# Interface1.net
KiCad netlist of a schematic drawn in Altium Designer
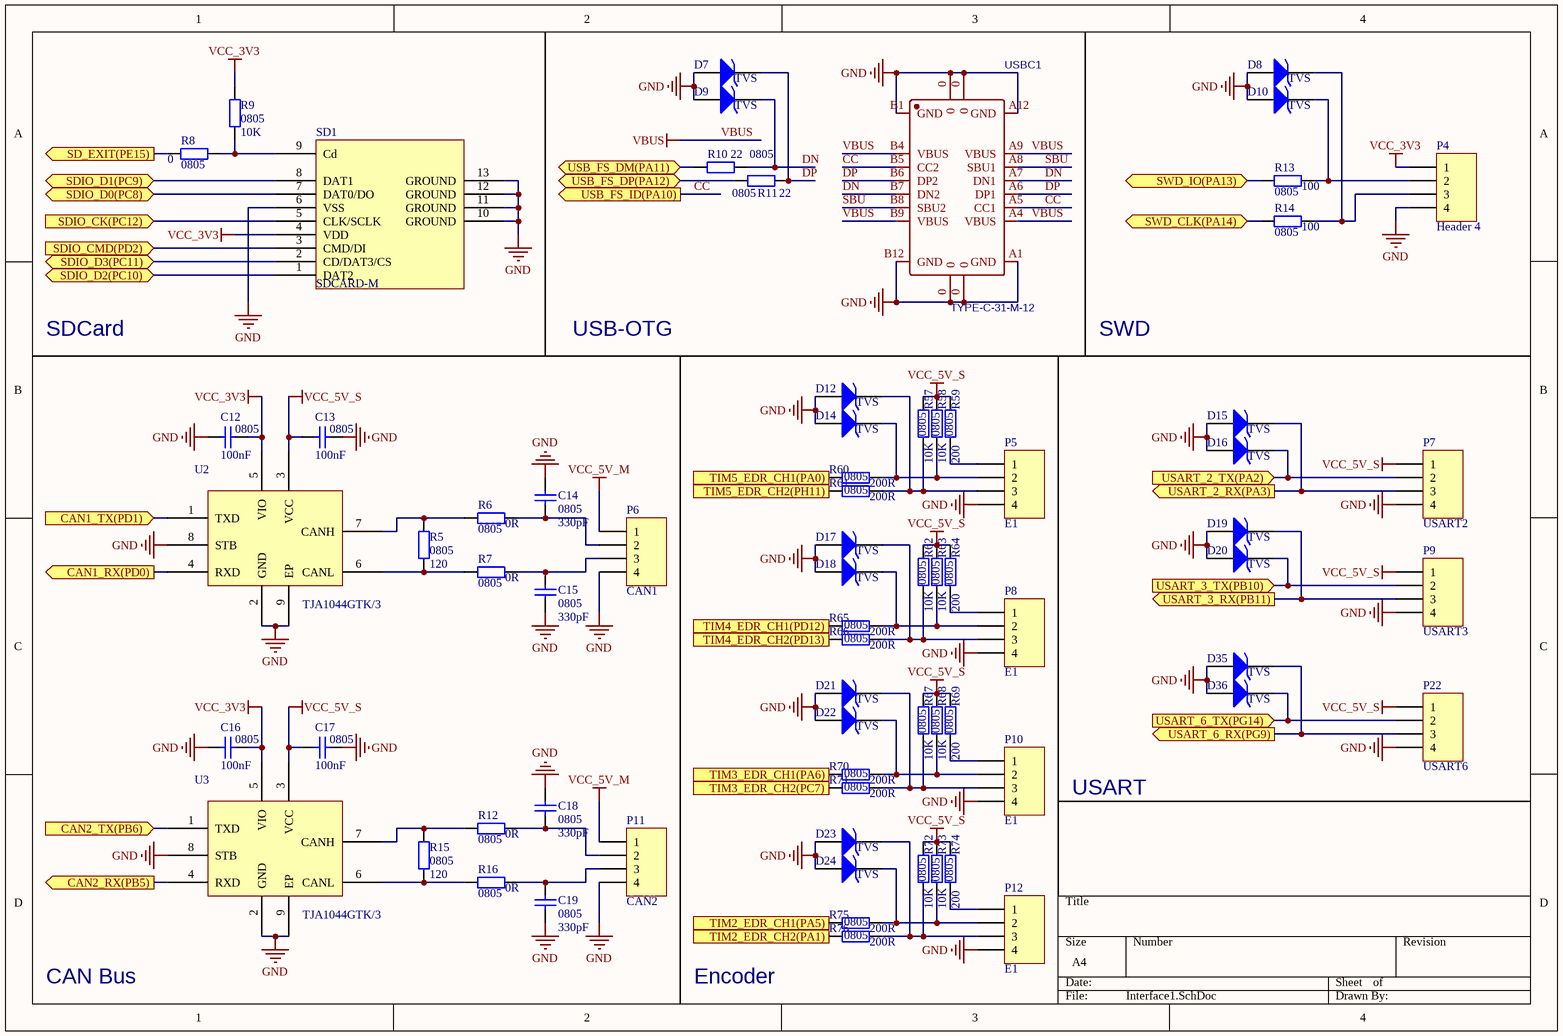
[diagram p0: Interface1.SchDoc]

(export (version "E")
  (design (tool "Eeschema 10.0.6"))
  (components
    (comp (ref "C12")
      (value "0805")
      (footprint "C 0805_M")
      (fields (field (name "ALTIUM_VALUE") "100nF"))
      (libsource (lib "QT") (part "CAP"))
    )
    (comp (ref "C13")
      (value "0805")
      (footprint "C 0805_M")
      (fields (field (name "ALTIUM_VALUE") "100nF"))
      (libsource (lib "QT") (part "CAP"))
    )
    (comp (ref "C14")
      (value "0805")
      (footprint "C 0805_M")
      (fields (field (name "ALTIUM_VALUE") "330pF"))
      (libsource (lib "QT") (part "CAP"))
    )
    (comp (ref "C15")
      (value "0805")
      (footprint "C 0805_M")
      (fields (field (name "ALTIUM_VALUE") "330pF"))
      (libsource (lib "QT") (part "CAP"))
    )
    (comp (ref "C16")
      (value "0805")
      (footprint "C 0805_M")
      (fields (field (name "ALTIUM_VALUE") "100nF"))
      (libsource (lib "QT") (part "CAP"))
    )
    (comp (ref "C17")
      (value "0805")
      (footprint "C 0805_M")
      (fields (field (name "ALTIUM_VALUE") "100nF"))
      (libsource (lib "QT") (part "CAP"))
    )
    (comp (ref "C18")
      (value "0805")
      (footprint "C 0805_M")
      (fields (field (name "ALTIUM_VALUE") "330pF"))
      (libsource (lib "QT") (part "CAP"))
    )
    (comp (ref "C19")
      (value "0805")
      (footprint "C 0805_M")
      (fields (field (name "ALTIUM_VALUE") "330pF"))
      (libsource (lib "QT") (part "CAP"))
    )
    (comp (ref "D7")
      (value "TVS")
      (footprint "SOD-523")
      (description "High Conductance Fast Diode")
      (fields (field (name "PUBLISHER") "Altium Limited"))
      (libsource (lib "QT") (part "D"))
    )
    (comp (ref "D8")
      (value "TVS")
      (footprint "SOD-523")
      (description "High Conductance Fast Diode")
      (fields (field (name "PUBLISHER") "Altium Limited"))
      (libsource (lib "QT") (part "D"))
    )
    (comp (ref "D9")
      (value "TVS")
      (footprint "SOD-523")
      (description "High Conductance Fast Diode")
      (fields (field (name "PUBLISHER") "Altium Limited"))
      (libsource (lib "QT") (part "D"))
    )
    (comp (ref "D10")
      (value "TVS")
      (footprint "SOD-523")
      (description "High Conductance Fast Diode")
      (fields (field (name "PUBLISHER") "Altium Limited"))
      (libsource (lib "QT") (part "D"))
    )
    (comp (ref "D12")
      (value "TVS")
      (footprint "SOD-523")
      (description "High Conductance Fast Diode")
      (fields (field (name "PUBLISHER") "Altium Limited"))
      (libsource (lib "QT") (part "D"))
    )
    (comp (ref "D14")
      (value "TVS")
      (footprint "SOD-523")
      (description "High Conductance Fast Diode")
      (fields (field (name "PUBLISHER") "Altium Limited"))
      (libsource (lib "QT") (part "D"))
    )
    (comp (ref "D15")
      (value "TVS")
      (footprint "SOD-523")
      (description "High Conductance Fast Diode")
      (fields (field (name "PUBLISHER") "Altium Limited"))
      (libsource (lib "QT") (part "D"))
    )
    (comp (ref "D16")
      (value "TVS")
      (footprint "SOD-523")
      (description "High Conductance Fast Diode")
      (fields (field (name "PUBLISHER") "Altium Limited"))
      (libsource (lib "QT") (part "D"))
    )
    (comp (ref "D17")
      (value "TVS")
      (footprint "SOD-523")
      (description "High Conductance Fast Diode")
      (fields (field (name "PUBLISHER") "Altium Limited"))
      (libsource (lib "QT") (part "D"))
    )
    (comp (ref "D18")
      (value "TVS")
      (footprint "SOD-523")
      (description "High Conductance Fast Diode")
      (fields (field (name "PUBLISHER") "Altium Limited"))
      (libsource (lib "QT") (part "D"))
    )
    (comp (ref "D19")
      (value "TVS")
      (footprint "SOD-523")
      (description "High Conductance Fast Diode")
      (fields (field (name "PUBLISHER") "Altium Limited"))
      (libsource (lib "QT") (part "D"))
    )
    (comp (ref "D20")
      (value "TVS")
      (footprint "SOD-523")
      (description "High Conductance Fast Diode")
      (fields (field (name "PUBLISHER") "Altium Limited"))
      (libsource (lib "QT") (part "D"))
    )
    (comp (ref "D21")
      (value "TVS")
      (footprint "SOD-523")
      (description "High Conductance Fast Diode")
      (fields (field (name "PUBLISHER") "Altium Limited"))
      (libsource (lib "QT") (part "D"))
    )
    (comp (ref "D22")
      (value "TVS")
      (footprint "SOD-523")
      (description "High Conductance Fast Diode")
      (fields (field (name "PUBLISHER") "Altium Limited"))
      (libsource (lib "QT") (part "D"))
    )
    (comp (ref "D23")
      (value "TVS")
      (footprint "SOD-523")
      (description "High Conductance Fast Diode")
      (fields (field (name "PUBLISHER") "Altium Limited"))
      (libsource (lib "QT") (part "D"))
    )
    (comp (ref "D24")
      (value "TVS")
      (footprint "SOD-523")
      (description "High Conductance Fast Diode")
      (fields (field (name "PUBLISHER") "Altium Limited"))
      (libsource (lib "QT") (part "D"))
    )
    (comp (ref "D35")
      (value "TVS")
      (footprint "SOD-523")
      (description "High Conductance Fast Diode")
      (fields (field (name "PUBLISHER") "Altium Limited"))
      (libsource (lib "QT") (part "D"))
    )
    (comp (ref "D36")
      (value "TVS")
      (footprint "SOD-523")
      (description "High Conductance Fast Diode")
      (fields (field (name "PUBLISHER") "Altium Limited"))
      (libsource (lib "QT") (part "D"))
    )
    (comp (ref "P4")
      (value "Header 4")
      (footprint "HDR2.54-LI-4P")
      (description "Header, 4-Pin")
      (fields (field (name "PUBLISHER") "Altium Limited"))
      (libsource (lib "QT") (part "Header 4"))
    )
    (comp (ref "P5")
      (value "E1")
      (footprint "HDR2.54-LI-4P")
      (description "Header, 4-Pin")
      (fields (field (name "PUBLISHER") "Altium Limited"))
      (libsource (lib "QT") (part "Header 4"))
    )
    (comp (ref "P6")
      (value "CAN1")
      (footprint "HDR2.54-LI-4P")
      (description "Header, 4-Pin")
      (fields (field (name "PUBLISHER") "Altium Limited"))
      (libsource (lib "QT") (part "Header 4"))
    )
    (comp (ref "P7")
      (value "USART2")
      (footprint "HDR2.54-LI-4P")
      (description "Header, 4-Pin")
      (fields (field (name "PUBLISHER") "Altium Limited"))
      (libsource (lib "QT") (part "Header 4"))
    )
    (comp (ref "P8")
      (value "E1")
      (footprint "HDR2.54-LI-4P")
      (description "Header, 4-Pin")
      (fields (field (name "PUBLISHER") "Altium Limited"))
      (libsource (lib "QT") (part "Header 4"))
    )
    (comp (ref "P9")
      (value "USART3")
      (footprint "HDR2.54-LI-4P")
      (description "Header, 4-Pin")
      (fields (field (name "PUBLISHER") "Altium Limited"))
      (libsource (lib "QT") (part "Header 4"))
    )
    (comp (ref "P10")
      (value "E1")
      (footprint "HDR2.54-LI-4P")
      (description "Header, 4-Pin")
      (fields (field (name "PUBLISHER") "Altium Limited"))
      (libsource (lib "QT") (part "Header 4"))
    )
    (comp (ref "P11")
      (value "CAN2")
      (footprint "HDR2.54-LI-4P")
      (description "Header, 4-Pin")
      (fields (field (name "PUBLISHER") "Altium Limited"))
      (libsource (lib "QT") (part "Header 4"))
    )
    (comp (ref "P12")
      (value "E1")
      (footprint "HDR2.54-LI-4P")
      (description "Header, 4-Pin")
      (fields (field (name "PUBLISHER") "Altium Limited"))
      (libsource (lib "QT") (part "Header 4"))
    )
    (comp (ref "P22")
      (value "USART6")
      (footprint "HDR2.54-LI-4P")
      (description "Header, 4-Pin")
      (fields (field (name "PUBLISHER") "Altium Limited"))
      (libsource (lib "QT") (part "Header 4"))
    )
    (comp (ref "R5")
      (value "0805")
      (footprint "R 0805_L")
      (description "Resistor")
      (fields (field (name "ALTIUM_VALUE") "120") (field (name "PUBLISHER") "Altium Limited"))
      (libsource (lib "QT") (part "RES2"))
    )
    (comp (ref "R6")
      (value "0805")
      (footprint "R 0805_L")
      (description "Resistor")
      (fields (field (name "ALTIUM_VALUE") "0R") (field (name "PUBLISHER") "Altium Limited"))
      (libsource (lib "") (part "RES2_1"))
    )
    (comp (ref "R7")
      (value "0805")
      (footprint "R 0805_L")
      (description "Resistor")
      (fields (field (name "ALTIUM_VALUE") "0R") (field (name "PUBLISHER") "Altium Limited"))
      (libsource (lib "") (part "RES2_1"))
    )
    (comp (ref "R8")
      (value "0805")
      (footprint "R 0805_L")
      (description "Resistor")
      (fields (field (name "ALTIUM_VALUE") "0") (field (name "PUBLISHER") "Altium Limited"))
      (libsource (lib "") (part "RES2_2"))
    )
    (comp (ref "R9")
      (value "0805")
      (footprint "R 0805_L")
      (description "Resistor")
      (fields (field (name "ALTIUM_VALUE") "10K") (field (name "PUBLISHER") "Altium Limited"))
      (libsource (lib "QT") (part "RES2"))
    )
    (comp (ref "R10")
      (value "0805")
      (footprint "R 0805_L")
      (description "Resistor")
      (fields (field (name "ALTIUM_VALUE") "22") (field (name "PUBLISHER") "Altium Limited"))
      (libsource (lib "") (part "RES2_2"))
    )
    (comp (ref "R11")
      (value "0805")
      (footprint "R 0805_L")
      (description "Resistor")
      (fields (field (name "ALTIUM_VALUE") "22") (field (name "PUBLISHER") "Altium Limited"))
      (libsource (lib "") (part "RES2_2"))
    )
    (comp (ref "R12")
      (value "0805")
      (footprint "R 0805_L")
      (description "Resistor")
      (fields (field (name "ALTIUM_VALUE") "0R") (field (name "PUBLISHER") "Altium Limited"))
      (libsource (lib "") (part "RES2_1"))
    )
    (comp (ref "R13")
      (value "0805")
      (footprint "R 0805_L")
      (description "Resistor")
      (fields (field (name "ALTIUM_VALUE") "100") (field (name "PUBLISHER") "Altium Limited"))
      (libsource (lib "") (part "RES2_2"))
    )
    (comp (ref "R14")
      (value "0805")
      (footprint "R 0805_L")
      (description "Resistor")
      (fields (field (name "ALTIUM_VALUE") "100") (field (name "PUBLISHER") "Altium Limited"))
      (libsource (lib "") (part "RES2_2"))
    )
    (comp (ref "R15")
      (value "0805")
      (footprint "R 0805_L")
      (description "Resistor")
      (fields (field (name "ALTIUM_VALUE") "120") (field (name "PUBLISHER") "Altium Limited"))
      (libsource (lib "QT") (part "RES2"))
    )
    (comp (ref "R16")
      (value "0805")
      (footprint "R 0805_L")
      (description "Resistor")
      (fields (field (name "ALTIUM_VALUE") "0R") (field (name "PUBLISHER") "Altium Limited"))
      (libsource (lib "") (part "RES2_1"))
    )
    (comp (ref "R57")
      (value "0805")
      (footprint "R 0805_L")
      (description "Resistor")
      (fields (field (name "ALTIUM_VALUE") "10K") (field (name "PUBLISHER") "Altium Limited"))
      (libsource (lib "QT") (part "RES2"))
    )
    (comp (ref "R58")
      (value "0805")
      (footprint "R 0805_L")
      (description "Resistor")
      (fields (field (name "ALTIUM_VALUE") "10K") (field (name "PUBLISHER") "Altium Limited"))
      (libsource (lib "QT") (part "RES2"))
    )
    (comp (ref "R59")
      (value "0805")
      (footprint "R 0805_L")
      (description "Resistor")
      (fields (field (name "ALTIUM_VALUE") "200") (field (name "PUBLISHER") "Altium Limited"))
      (libsource (lib "QT") (part "RES2"))
    )
    (comp (ref "R60")
      (value "0805")
      (footprint "R 0805_L")
      (description "Resistor")
      (fields (field (name "ALTIUM_VALUE") "200R") (field (name "PUBLISHER") "Altium Limited"))
      (libsource (lib "") (part "RES2_2"))
    )
    (comp (ref "R61")
      (value "0805")
      (footprint "R 0805_L")
      (description "Resistor")
      (fields (field (name "ALTIUM_VALUE") "200R") (field (name "PUBLISHER") "Altium Limited"))
      (libsource (lib "") (part "RES2_2"))
    )
    (comp (ref "R62")
      (value "0805")
      (footprint "R 0805_L")
      (description "Resistor")
      (fields (field (name "ALTIUM_VALUE") "10K") (field (name "PUBLISHER") "Altium Limited"))
      (libsource (lib "QT") (part "RES2"))
    )
    (comp (ref "R63")
      (value "0805")
      (footprint "R 0805_L")
      (description "Resistor")
      (fields (field (name "ALTIUM_VALUE") "10K") (field (name "PUBLISHER") "Altium Limited"))
      (libsource (lib "QT") (part "RES2"))
    )
    (comp (ref "R64")
      (value "0805")
      (footprint "R 0805_L")
      (description "Resistor")
      (fields (field (name "ALTIUM_VALUE") "200") (field (name "PUBLISHER") "Altium Limited"))
      (libsource (lib "QT") (part "RES2"))
    )
    (comp (ref "R65")
      (value "0805")
      (footprint "R 0805_L")
      (description "Resistor")
      (fields (field (name "ALTIUM_VALUE") "200R") (field (name "PUBLISHER") "Altium Limited"))
      (libsource (lib "") (part "RES2_2"))
    )
    (comp (ref "R66")
      (value "0805")
      (footprint "R 0805_L")
      (description "Resistor")
      (fields (field (name "ALTIUM_VALUE") "200R") (field (name "PUBLISHER") "Altium Limited"))
      (libsource (lib "") (part "RES2_2"))
    )
    (comp (ref "R67")
      (value "0805")
      (footprint "R 0805_L")
      (description "Resistor")
      (fields (field (name "ALTIUM_VALUE") "10K") (field (name "PUBLISHER") "Altium Limited"))
      (libsource (lib "QT") (part "RES2"))
    )
    (comp (ref "R68")
      (value "0805")
      (footprint "R 0805_L")
      (description "Resistor")
      (fields (field (name "ALTIUM_VALUE") "10K") (field (name "PUBLISHER") "Altium Limited"))
      (libsource (lib "QT") (part "RES2"))
    )
    (comp (ref "R69")
      (value "0805")
      (footprint "R 0805_L")
      (description "Resistor")
      (fields (field (name "ALTIUM_VALUE") "200") (field (name "PUBLISHER") "Altium Limited"))
      (libsource (lib "QT") (part "RES2"))
    )
    (comp (ref "R70")
      (value "0805")
      (footprint "R 0805_L")
      (description "Resistor")
      (fields (field (name "ALTIUM_VALUE") "200R") (field (name "PUBLISHER") "Altium Limited"))
      (libsource (lib "") (part "RES2_2"))
    )
    (comp (ref "R71")
      (value "0805")
      (footprint "R 0805_L")
      (description "Resistor")
      (fields (field (name "ALTIUM_VALUE") "200R") (field (name "PUBLISHER") "Altium Limited"))
      (libsource (lib "") (part "RES2_2"))
    )
    (comp (ref "R72")
      (value "0805")
      (footprint "R 0805_L")
      (description "Resistor")
      (fields (field (name "ALTIUM_VALUE") "10K") (field (name "PUBLISHER") "Altium Limited"))
      (libsource (lib "QT") (part "RES2"))
    )
    (comp (ref "R73")
      (value "0805")
      (footprint "R 0805_L")
      (description "Resistor")
      (fields (field (name "ALTIUM_VALUE") "10K") (field (name "PUBLISHER") "Altium Limited"))
      (libsource (lib "QT") (part "RES2"))
    )
    (comp (ref "R74")
      (value "0805")
      (footprint "R 0805_L")
      (description "Resistor")
      (fields (field (name "ALTIUM_VALUE") "200") (field (name "PUBLISHER") "Altium Limited"))
      (libsource (lib "QT") (part "RES2"))
    )
    (comp (ref "R75")
      (value "0805")
      (footprint "R 0805_L")
      (description "Resistor")
      (fields (field (name "ALTIUM_VALUE") "200R") (field (name "PUBLISHER") "Altium Limited"))
      (libsource (lib "") (part "RES2_2"))
    )
    (comp (ref "R76")
      (value "0805")
      (footprint "R 0805_L")
      (description "Resistor")
      (fields (field (name "ALTIUM_VALUE") "200R") (field (name "PUBLISHER") "Altium Limited"))
      (libsource (lib "") (part "RES2_2"))
    )
    (comp (ref "SD1")
      (value "SDCARD-M")
      (footprint "SDCARD-M")
      (description "TF卡槽")
      (libsource (lib "Fszhang") (part "SDCARD-M"))
    )
    (comp (ref "U2")
      (value "TJA1044GTK/3")
      (footprint "HVSON8")
      (libsource (lib "常用元件库") (part "TJA1044GTK/3"))
    )
    (comp (ref "U3")
      (value "TJA1044GTK/3")
      (footprint "HVSON8")
      (libsource (lib "常用元件库") (part "TJA1044GTK/3"))
    )
    (comp (ref "USBC1")
      (value "TYPE-C-31-M-12")
      (footprint "TYPE-C-USB-17")
      (libsource (lib "Interface") (part "TYPE-C-31-M-12"))
    )
  )
  (nets
    (net (code "1") (name "/CAN1_RX(PD0)") (class "Default")
      (node (ref "U2") (pin "4") (pinfunction "RXD_4") (pintype "passive"))
    )
    (net (code "2") (name "/CAN1_TX(PD1)") (class "Default")
      (node (ref "U2") (pin "1") (pinfunction "TXD_1") (pintype "passive"))
    )
    (net (code "3") (name "/CAN2_RX(PB5)") (class "Default")
      (node (ref "U3") (pin "4") (pinfunction "RXD_4") (pintype "passive"))
    )
    (net (code "4") (name "/CAN2_TX(PB6)") (class "Default")
      (node (ref "U3") (pin "1") (pinfunction "TXD_1") (pintype "passive"))
    )
    (net (code "5") (name "/CC") (class "Default")
      (node (ref "USBC1") (pin "A5") (pinfunction "CC1_A5") (pintype "passive"))
      (node (ref "USBC1") (pin "B5") (pinfunction "CC2_B5") (pintype "passive"))
    )
    (net (code "6") (name "/DN") (class "Default")
      (node (ref "D9") (pin "2") (pinfunction "K_2") (pintype "passive"))
      (node (ref "R10") (pin "2") (pinfunction "2_2") (pintype "passive"))
      (node (ref "USBC1") (pin "A7") (pinfunction "DN1_A7") (pintype "passive"))
      (node (ref "USBC1") (pin "B7") (pinfunction "DN2_B7") (pintype "passive"))
    )
    (net (code "7") (name "/DP") (class "Default")
      (node (ref "D7") (pin "2") (pinfunction "K_2") (pintype "passive"))
      (node (ref "R11") (pin "2") (pinfunction "2_2") (pintype "passive"))
      (node (ref "USBC1") (pin "A6") (pinfunction "DP1_A6") (pintype "passive"))
      (node (ref "USBC1") (pin "B6") (pinfunction "DP2_B6") (pintype "passive"))
    )
    (net (code "8") (name "/SBU") (class "Default")
      (node (ref "USBC1") (pin "A8") (pinfunction "SBU1_A8") (pintype "passive"))
      (node (ref "USBC1") (pin "B8") (pinfunction "SBU2_B8") (pintype "passive"))
    )
    (net (code "9") (name "/SDIO_CK(PC12)") (class "Default")
      (node (ref "SD1") (pin "5") (pinfunction "CLK/SCLK_5") (pintype "passive"))
    )
    (net (code "10") (name "/SDIO_CMD(PD2)") (class "Default")
      (node (ref "SD1") (pin "3") (pinfunction "CMD/DI_3") (pintype "passive"))
    )
    (net (code "11") (name "/SDIO_D0(PC8)") (class "Default")
      (node (ref "SD1") (pin "7") (pinfunction "DAT0/DO_7") (pintype "passive"))
    )
    (net (code "12") (name "/SDIO_D1(PC9)") (class "Default")
      (node (ref "SD1") (pin "8") (pinfunction "DAT1_8") (pintype "passive"))
    )
    (net (code "13") (name "/SDIO_D2(PC10)") (class "Default")
      (node (ref "SD1") (pin "1") (pinfunction "DAT2_1") (pintype "passive"))
    )
    (net (code "14") (name "/SDIO_D3(PC11)") (class "Default")
      (node (ref "SD1") (pin "2") (pinfunction "CD/DAT3/CS_2") (pintype "passive"))
    )
    (net (code "15") (name "/SD_EXIT(PE15)") (class "Default")
      (node (ref "R8") (pin "1") (pinfunction "1_1") (pintype "passive"))
    )
    (net (code "16") (name "/SWD_CLK(PA14)") (class "Default")
      (node (ref "R14") (pin "1") (pinfunction "1_1") (pintype "passive"))
    )
    (net (code "17") (name "/SWD_IO(PA13)") (class "Default")
      (node (ref "R13") (pin "1") (pinfunction "1_1") (pintype "passive"))
    )
    (net (code "18") (name "/TIM2_EDR_CH1(PA5)") (class "Default")
      (node (ref "R75") (pin "1") (pinfunction "1_1") (pintype "passive"))
    )
    (net (code "19") (name "/TIM2_EDR_CH2(PA1)") (class "Default")
      (node (ref "R76") (pin "1") (pinfunction "1_1") (pintype "passive"))
    )
    (net (code "20") (name "/TIM3_EDR_CH1(PA6)") (class "Default")
      (node (ref "R70") (pin "1") (pinfunction "1_1") (pintype "passive"))
    )
    (net (code "21") (name "/TIM3_EDR_CH2(PC7)") (class "Default")
      (node (ref "R71") (pin "1") (pinfunction "1_1") (pintype "passive"))
    )
    (net (code "22") (name "/TIM4_EDR_CH1(PD12)") (class "Default")
      (node (ref "R65") (pin "1") (pinfunction "1_1") (pintype "passive"))
    )
    (net (code "23") (name "/TIM4_EDR_CH2(PD13)") (class "Default")
      (node (ref "R66") (pin "1") (pinfunction "1_1") (pintype "passive"))
    )
    (net (code "24") (name "/TIM5_EDR_CH1(PA0)") (class "Default")
      (node (ref "R60") (pin "1") (pinfunction "1_1") (pintype "passive"))
    )
    (net (code "25") (name "/TIM5_EDR_CH2(PH11)") (class "Default")
      (node (ref "R61") (pin "1") (pinfunction "1_1") (pintype "passive"))
    )
    (net (code "26") (name "/USART_2_RX(PA3)") (class "Default")
      (node (ref "D15") (pin "2") (pinfunction "K_2") (pintype "passive"))
      (node (ref "P7") (pin "3") (pinfunction "3_3") (pintype "passive"))
    )
    (net (code "27") (name "/USART_2_TX(PA2)") (class "Default")
      (node (ref "D16") (pin "2") (pinfunction "K_2") (pintype "passive"))
      (node (ref "P7") (pin "2") (pinfunction "2_2") (pintype "passive"))
    )
    (net (code "28") (name "/USART_3_RX(PB11)") (class "Default")
      (node (ref "D19") (pin "2") (pinfunction "K_2") (pintype "passive"))
      (node (ref "P9") (pin "3") (pinfunction "3_3") (pintype "passive"))
    )
    (net (code "29") (name "/USART_3_TX(PB10)") (class "Default")
      (node (ref "D20") (pin "2") (pinfunction "K_2") (pintype "passive"))
      (node (ref "P9") (pin "2") (pinfunction "2_2") (pintype "passive"))
    )
    (net (code "30") (name "/USART_6_RX(PG9)") (class "Default")
      (node (ref "D35") (pin "2") (pinfunction "K_2") (pintype "passive"))
      (node (ref "P22") (pin "3") (pinfunction "3_3") (pintype "passive"))
    )
    (net (code "31") (name "/USART_6_TX(PG14)") (class "Default")
      (node (ref "D36") (pin "2") (pinfunction "K_2") (pintype "passive"))
      (node (ref "P22") (pin "2") (pinfunction "2_2") (pintype "passive"))
    )
    (net (code "32") (name "/USB_FS_DM(PA11)") (class "Default")
      (node (ref "R10") (pin "1") (pinfunction "1_1") (pintype "passive"))
    )
    (net (code "33") (name "/USB_FS_DP(PA12)") (class "Default")
      (node (ref "R11") (pin "1") (pinfunction "1_1") (pintype "passive"))
    )
    (net (code "34") (name "GND") (class "Default")
      (node (ref "C12") (pin "1") (pinfunction "1_1") (pintype "passive"))
      (node (ref "C13") (pin "2") (pinfunction "2_2") (pintype "passive"))
      (node (ref "C14") (pin "2") (pinfunction "2_2") (pintype "passive"))
      (node (ref "C15") (pin "1") (pinfunction "1_1") (pintype "passive"))
      (node (ref "C16") (pin "1") (pinfunction "1_1") (pintype "passive"))
      (node (ref "C17") (pin "2") (pinfunction "2_2") (pintype "passive"))
      (node (ref "C18") (pin "2") (pinfunction "2_2") (pintype "passive"))
      (node (ref "C19") (pin "1") (pinfunction "1_1") (pintype "passive"))
      (node (ref "D10") (pin "1") (pinfunction "A_1") (pintype "passive"))
      (node (ref "D12") (pin "1") (pinfunction "A_1") (pintype "passive"))
      (node (ref "D14") (pin "1") (pinfunction "A_1") (pintype "passive"))
      (node (ref "D15") (pin "1") (pinfunction "A_1") (pintype "passive"))
      (node (ref "D16") (pin "1") (pinfunction "A_1") (pintype "passive"))
      (node (ref "D17") (pin "1") (pinfunction "A_1") (pintype "passive"))
      (node (ref "D18") (pin "1") (pinfunction "A_1") (pintype "passive"))
      (node (ref "D19") (pin "1") (pinfunction "A_1") (pintype "passive"))
      (node (ref "D20") (pin "1") (pinfunction "A_1") (pintype "passive"))
      (node (ref "D21") (pin "1") (pinfunction "A_1") (pintype "passive"))
      (node (ref "D22") (pin "1") (pinfunction "A_1") (pintype "passive"))
      (node (ref "D23") (pin "1") (pinfunction "A_1") (pintype "passive"))
      (node (ref "D24") (pin "1") (pinfunction "A_1") (pintype "passive"))
      (node (ref "D35") (pin "1") (pinfunction "A_1") (pintype "passive"))
      (node (ref "D36") (pin "1") (pinfunction "A_1") (pintype "passive"))
      (node (ref "D7") (pin "1") (pinfunction "A_1") (pintype "passive"))
      (node (ref "D8") (pin "1") (pinfunction "A_1") (pintype "passive"))
      (node (ref "D9") (pin "1") (pinfunction "A_1") (pintype "passive"))
      (node (ref "P10") (pin "4") (pinfunction "4_4") (pintype "passive"))
      (node (ref "P11") (pin "4") (pinfunction "4_4") (pintype "passive"))
      (node (ref "P12") (pin "4") (pinfunction "4_4") (pintype "passive"))
      (node (ref "P22") (pin "4") (pinfunction "4_4") (pintype "passive"))
      (node (ref "P4") (pin "4") (pinfunction "4_4") (pintype "passive"))
      (node (ref "P5") (pin "4") (pinfunction "4_4") (pintype "passive"))
      (node (ref "P6") (pin "4") (pinfunction "4_4") (pintype "passive"))
      (node (ref "P7") (pin "4") (pinfunction "4_4") (pintype "passive"))
      (node (ref "P8") (pin "4") (pinfunction "4_4") (pintype "passive"))
      (node (ref "P9") (pin "4") (pinfunction "4_4") (pintype "passive"))
      (node (ref "SD1") (pin "10") (pinfunction "GROUND_10") (pintype "passive"))
      (node (ref "SD1") (pin "11") (pinfunction "GROUND_11") (pintype "passive"))
      (node (ref "SD1") (pin "12") (pinfunction "GROUND_12") (pintype "passive"))
      (node (ref "SD1") (pin "13") (pinfunction "GROUND_13") (pintype "passive"))
      (node (ref "SD1") (pin "6") (pinfunction "VSS_6") (pintype "passive"))
      (node (ref "U2") (pin "2") (pinfunction "GND_2") (pintype "passive"))
      (node (ref "U2") (pin "8") (pinfunction "STB_8") (pintype "passive"))
      (node (ref "U2") (pin "9") (pinfunction "EP_9") (pintype "passive"))
      (node (ref "U3") (pin "2") (pinfunction "GND_2") (pintype "passive"))
      (node (ref "U3") (pin "8") (pinfunction "STB_8") (pintype "passive"))
      (node (ref "U3") (pin "9") (pinfunction "EP_9") (pintype "passive"))
      (node (ref "USBC1") (pin "0") (pinfunction "0_0") (pintype "passive"))
      (node (ref "USBC1") (pin "A1") (pinfunction "GND_A1") (pintype "passive"))
      (node (ref "USBC1") (pin "A12") (pinfunction "GND_A12") (pintype "passive"))
      (node (ref "USBC1") (pin "B1") (pinfunction "GND_B1") (pintype "passive"))
      (node (ref "USBC1") (pin "B12") (pinfunction "GND_B12") (pintype "passive"))
    )
    (net (code "35") (name "Net-(C14-Pad1)") (class "Default")
      (node (ref "C14") (pin "1") (pinfunction "1_1") (pintype "passive"))
      (node (ref "P6") (pin "2") (pinfunction "2_2") (pintype "passive"))
      (node (ref "R6") (pin "1") (pinfunction "1_1") (pintype "passive"))
    )
    (net (code "36") (name "Net-(C15-Pad2)") (class "Default")
      (node (ref "C15") (pin "2") (pinfunction "2_2") (pintype "passive"))
      (node (ref "P6") (pin "3") (pinfunction "3_3") (pintype "passive"))
      (node (ref "R7") (pin "1") (pinfunction "1_1") (pintype "passive"))
    )
    (net (code "37") (name "Net-(C18-Pad1)") (class "Default")
      (node (ref "C18") (pin "1") (pinfunction "1_1") (pintype "passive"))
      (node (ref "P11") (pin "2") (pinfunction "2_2") (pintype "passive"))
      (node (ref "R12") (pin "1") (pinfunction "1_1") (pintype "passive"))
    )
    (net (code "38") (name "Net-(C19-Pad2)") (class "Default")
      (node (ref "C19") (pin "2") (pinfunction "2_2") (pintype "passive"))
      (node (ref "P11") (pin "3") (pinfunction "3_3") (pintype "passive"))
      (node (ref "R16") (pin "1") (pinfunction "1_1") (pintype "passive"))
    )
    (net (code "39") (name "Net-(D8-K)") (class "Default")
      (node (ref "D8") (pin "2") (pinfunction "K_2") (pintype "passive"))
      (node (ref "P4") (pin "3") (pinfunction "3_3") (pintype "passive"))
      (node (ref "R14") (pin "2") (pinfunction "2_2") (pintype "passive"))
    )
    (net (code "40") (name "Net-(D10-K)") (class "Default")
      (node (ref "D10") (pin "2") (pinfunction "K_2") (pintype "passive"))
      (node (ref "P4") (pin "2") (pinfunction "2_2") (pintype "passive"))
      (node (ref "R13") (pin "2") (pinfunction "2_2") (pintype "passive"))
    )
    (net (code "41") (name "Net-(D12-K)") (class "Default")
      (node (ref "D12") (pin "2") (pinfunction "K_2") (pintype "passive"))
      (node (ref "P5") (pin "3") (pinfunction "3_3") (pintype "passive"))
      (node (ref "R57") (pin "1") (pinfunction "1_1") (pintype "passive"))
      (node (ref "R61") (pin "2") (pinfunction "2_2") (pintype "passive"))
    )
    (net (code "42") (name "Net-(D14-K)") (class "Default")
      (node (ref "D14") (pin "2") (pinfunction "K_2") (pintype "passive"))
      (node (ref "P5") (pin "2") (pinfunction "2_2") (pintype "passive"))
      (node (ref "R58") (pin "1") (pinfunction "1_1") (pintype "passive"))
      (node (ref "R60") (pin "2") (pinfunction "2_2") (pintype "passive"))
    )
    (net (code "43") (name "Net-(D17-K)") (class "Default")
      (node (ref "D17") (pin "2") (pinfunction "K_2") (pintype "passive"))
      (node (ref "P8") (pin "3") (pinfunction "3_3") (pintype "passive"))
      (node (ref "R62") (pin "1") (pinfunction "1_1") (pintype "passive"))
      (node (ref "R66") (pin "2") (pinfunction "2_2") (pintype "passive"))
    )
    (net (code "44") (name "Net-(D18-K)") (class "Default")
      (node (ref "D18") (pin "2") (pinfunction "K_2") (pintype "passive"))
      (node (ref "P8") (pin "2") (pinfunction "2_2") (pintype "passive"))
      (node (ref "R63") (pin "1") (pinfunction "1_1") (pintype "passive"))
      (node (ref "R65") (pin "2") (pinfunction "2_2") (pintype "passive"))
    )
    (net (code "45") (name "Net-(D21-K)") (class "Default")
      (node (ref "D21") (pin "2") (pinfunction "K_2") (pintype "passive"))
      (node (ref "P10") (pin "3") (pinfunction "3_3") (pintype "passive"))
      (node (ref "R67") (pin "1") (pinfunction "1_1") (pintype "passive"))
      (node (ref "R71") (pin "2") (pinfunction "2_2") (pintype "passive"))
    )
    (net (code "46") (name "Net-(D22-K)") (class "Default")
      (node (ref "D22") (pin "2") (pinfunction "K_2") (pintype "passive"))
      (node (ref "P10") (pin "2") (pinfunction "2_2") (pintype "passive"))
      (node (ref "R68") (pin "1") (pinfunction "1_1") (pintype "passive"))
      (node (ref "R70") (pin "2") (pinfunction "2_2") (pintype "passive"))
    )
    (net (code "47") (name "Net-(D23-K)") (class "Default")
      (node (ref "D23") (pin "2") (pinfunction "K_2") (pintype "passive"))
      (node (ref "P12") (pin "3") (pinfunction "3_3") (pintype "passive"))
      (node (ref "R72") (pin "1") (pinfunction "1_1") (pintype "passive"))
      (node (ref "R76") (pin "2") (pinfunction "2_2") (pintype "passive"))
    )
    (net (code "48") (name "Net-(D24-K)") (class "Default")
      (node (ref "D24") (pin "2") (pinfunction "K_2") (pintype "passive"))
      (node (ref "P12") (pin "2") (pinfunction "2_2") (pintype "passive"))
      (node (ref "R73") (pin "1") (pinfunction "1_1") (pintype "passive"))
      (node (ref "R75") (pin "2") (pinfunction "2_2") (pintype "passive"))
    )
    (net (code "49") (name "Net-(P5-Pad1)") (class "Default")
      (node (ref "P5") (pin "1") (pinfunction "1_1") (pintype "passive"))
      (node (ref "R59") (pin "1") (pinfunction "1_1") (pintype "passive"))
    )
    (net (code "50") (name "Net-(P8-Pad1)") (class "Default")
      (node (ref "P8") (pin "1") (pinfunction "1_1") (pintype "passive"))
      (node (ref "R64") (pin "1") (pinfunction "1_1") (pintype "passive"))
    )
    (net (code "51") (name "Net-(P10-Pad1)") (class "Default")
      (node (ref "P10") (pin "1") (pinfunction "1_1") (pintype "passive"))
      (node (ref "R69") (pin "1") (pinfunction "1_1") (pintype "passive"))
    )
    (net (code "52") (name "Net-(P12-Pad1)") (class "Default")
      (node (ref "P12") (pin "1") (pinfunction "1_1") (pintype "passive"))
      (node (ref "R74") (pin "1") (pinfunction "1_1") (pintype "passive"))
    )
    (net (code "53") (name "Net-(SD1-Cd)") (class "Default")
      (node (ref "R8") (pin "2") (pinfunction "2_2") (pintype "passive"))
      (node (ref "R9") (pin "1") (pinfunction "1_1") (pintype "passive"))
      (node (ref "SD1") (pin "9") (pinfunction "Cd_9") (pintype "passive"))
    )
    (net (code "54") (name "Net-(U2-CANH)") (class "Default")
      (node (ref "R5") (pin "2") (pinfunction "2_2") (pintype "passive"))
      (node (ref "R6") (pin "2") (pinfunction "2_2") (pintype "passive"))
      (node (ref "U2") (pin "7") (pinfunction "CANH_7") (pintype "passive"))
    )
    (net (code "55") (name "Net-(U2-CANL)") (class "Default")
      (node (ref "R5") (pin "1") (pinfunction "1_1") (pintype "passive"))
      (node (ref "R7") (pin "2") (pinfunction "2_2") (pintype "passive"))
      (node (ref "U2") (pin "6") (pinfunction "CANL_6") (pintype "passive"))
    )
    (net (code "56") (name "Net-(U3-CANH)") (class "Default")
      (node (ref "R12") (pin "2") (pinfunction "2_2") (pintype "passive"))
      (node (ref "R15") (pin "2") (pinfunction "2_2") (pintype "passive"))
      (node (ref "U3") (pin "7") (pinfunction "CANH_7") (pintype "passive"))
    )
    (net (code "57") (name "Net-(U3-CANL)") (class "Default")
      (node (ref "R15") (pin "1") (pinfunction "1_1") (pintype "passive"))
      (node (ref "R16") (pin "2") (pinfunction "2_2") (pintype "passive"))
      (node (ref "U3") (pin "6") (pinfunction "CANL_6") (pintype "passive"))
    )
    (net (code "58") (name "VBUS") (class "Default")
      (node (ref "USBC1") (pin "A4") (pinfunction "VBUS_A4") (pintype "passive"))
      (node (ref "USBC1") (pin "A9") (pinfunction "VBUS_A9") (pintype "passive"))
      (node (ref "USBC1") (pin "B4") (pinfunction "VBUS_B4") (pintype "passive"))
      (node (ref "USBC1") (pin "B9") (pinfunction "VBUS_B9") (pintype "passive"))
    )
    (net (code "59") (name "VCC_3V3") (class "Default")
      (node (ref "C12") (pin "2") (pinfunction "2_2") (pintype "passive"))
      (node (ref "C16") (pin "2") (pinfunction "2_2") (pintype "passive"))
      (node (ref "P4") (pin "1") (pinfunction "1_1") (pintype "passive"))
      (node (ref "R9") (pin "2") (pinfunction "2_2") (pintype "passive"))
      (node (ref "SD1") (pin "4") (pinfunction "VDD_4") (pintype "passive"))
      (node (ref "U2") (pin "5") (pinfunction "VIO_5") (pintype "passive"))
      (node (ref "U3") (pin "5") (pinfunction "VIO_5") (pintype "passive"))
    )
    (net (code "60") (name "VCC_5V_M") (class "Default")
      (node (ref "P11") (pin "1") (pinfunction "1_1") (pintype "passive"))
      (node (ref "P6") (pin "1") (pinfunction "1_1") (pintype "passive"))
    )
    (net (code "61") (name "VCC_5V_S") (class "Default")
      (node (ref "C13") (pin "1") (pinfunction "1_1") (pintype "passive"))
      (node (ref "C17") (pin "1") (pinfunction "1_1") (pintype "passive"))
      (node (ref "P22") (pin "1") (pinfunction "1_1") (pintype "passive"))
      (node (ref "P7") (pin "1") (pinfunction "1_1") (pintype "passive"))
      (node (ref "P9") (pin "1") (pinfunction "1_1") (pintype "passive"))
      (node (ref "R57") (pin "2") (pinfunction "2_2") (pintype "passive"))
      (node (ref "R58") (pin "2") (pinfunction "2_2") (pintype "passive"))
      (node (ref "R59") (pin "2") (pinfunction "2_2") (pintype "passive"))
      (node (ref "R62") (pin "2") (pinfunction "2_2") (pintype "passive"))
      (node (ref "R63") (pin "2") (pinfunction "2_2") (pintype "passive"))
      (node (ref "R64") (pin "2") (pinfunction "2_2") (pintype "passive"))
      (node (ref "R67") (pin "2") (pinfunction "2_2") (pintype "passive"))
      (node (ref "R68") (pin "2") (pinfunction "2_2") (pintype "passive"))
      (node (ref "R69") (pin "2") (pinfunction "2_2") (pintype "passive"))
      (node (ref "R72") (pin "2") (pinfunction "2_2") (pintype "passive"))
      (node (ref "R73") (pin "2") (pinfunction "2_2") (pintype "passive"))
      (node (ref "R74") (pin "2") (pinfunction "2_2") (pintype "passive"))
      (node (ref "U2") (pin "3") (pinfunction "VCC_3") (pintype "passive"))
      (node (ref "U3") (pin "3") (pinfunction "VCC_3") (pintype "passive"))
    )
  )
)
